# programming.net
KiCad netlist of a schematic drawn in Altium Designer
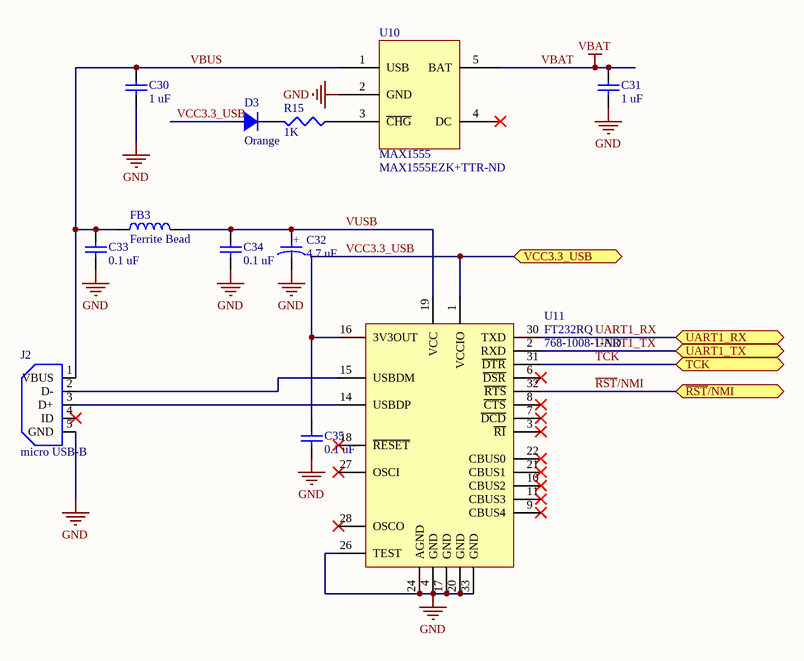
[diagram p0: programming.SchDoc]

(export (version "E")
  (design (tool "Eeschema 10.0.6"))
  (components
    (comp (ref "C30")
      (value "1 uF")
      (footprint "0402")
      (description "Ceramic capacitor, 1 uF, 0402 package")
      (fields (field (name "TOLERANCE") "10%") (field (name "Comment") "Ceramic capacitor"))
      (libsource (lib "rlc") (part "C_1u_0402_ceramic"))
    )
    (comp (ref "C31")
      (value "1 uF")
      (footprint "0402")
      (description "Ceramic capacitor, 1 uF, 0402 package")
      (fields (field (name "TOLERANCE") "10%") (field (name "Comment") "Ceramic capacitor"))
      (libsource (lib "rlc") (part "C_1u_0402_ceramic"))
    )
    (comp (ref "C32")
      (value "4.7 uF")
      (footprint "0603 - Polar Marking")
      (description "Tantalum capacitor, 4.7 uF, 0603 package")
      (fields (field (name "TOLERANCE") "20%") (field (name "Comment") "Tantalum capacitor"))
      (libsource (lib "rlc") (part "C_4.7u_0603_tantalum"))
    )
    (comp (ref "C33")
      (value "0.1 uF")
      (footprint "0402")
      (description "Ceramic capacitor, 0.1u, 0402 package")
      (fields (field (name "TOLERANCE") "10%") (field (name "Comment") "Ceramic capacitor"))
      (libsource (lib "rlc") (part "C_0.1u_0402_ceramic"))
    )
    (comp (ref "C34")
      (value "0.1 uF")
      (footprint "0402")
      (description "Ceramic capacitor, 0.1u, 0402 package")
      (fields (field (name "TOLERANCE") "10%") (field (name "Comment") "Ceramic capacitor"))
      (libsource (lib "rlc") (part "C_0.1u_0402_ceramic"))
    )
    (comp (ref "C35")
      (value "0.1 uF")
      (footprint "0402")
      (description "Ceramic capacitor, 0.1u, 0402 package")
      (fields (field (name "TOLERANCE") "10%") (field (name "Comment") "Ceramic capacitor"))
      (libsource (lib "rlc") (part "C_0.1u_0402_ceramic"))
    )
    (comp (ref "D3")
      (value "LED, Orange")
      (footprint "0402 - DIODE")
      (description "LED, Orange, 0402")
      (fields (field (name "COLOR") "Orange"))
      (libsource (lib "rlc") (part "D_LED_ORANGE_0402"))
    )
    (comp (ref "FB3")
      (value "Ferrite Bead")
      (footprint "0402")
      (description "Ferrite Bead, 150 mA, 0402 package")
      (libsource (lib "rlc") (part "FB_150mA_0402"))
    )
    (comp (ref "J2")
      (value "micro USB-B")
      (footprint "Micro USB-B")
      (description "CONN USB MICRO B RECPT SMT R/A")
      (libsource (lib "opo") (part "Micro USB"))
    )
    (comp (ref "R15")
      (value "1K")
      (footprint "0402")
      (description "Chip resistor, 1K, 0402 package")
      (fields (field (name "TOLERANCE") "1%") (field (name "POWER") "1/16 W"))
      (libsource (lib "rlc") (part "R_1K_0402"))
    )
    (comp (ref "U10")
      (value "MAX1555")
      (footprint "SOT23-5")
      (description "3 Dual-Input USB/AC Adapter 1-Cell Li+  Battery Chargers")
      (fields (field (name "SUPPLIER PART NUMBER 1") "MAX1555EZK+TTR-ND"))
      (libsource (lib "opo") (part "MAX1555"))
    )
    (comp (ref "U11")
      (value "FT232RQ")
      (footprint "QFN-32")
      (description "FT232R USB UART")
      (fields (field (name "SUPPLIER PART NUMBER 1") "768-1008-1-ND"))
      (libsource (lib "opo") (part "IC_FT232RQ"))
    )
  )
  (nets
    (net (code "1") (name "/TCK") (class "Default")
      (node (ref "U11") (pin "31") (pinfunction "~{DTR}_31") (pintype "passive"))
    )
    (net (code "2") (name "/UART1_RX") (class "Default")
      (node (ref "U11") (pin "30") (pinfunction "TXD_30") (pintype "passive"))
    )
    (net (code "3") (name "/UART1_TX") (class "Default")
      (node (ref "U11") (pin "2") (pinfunction "RXD_2") (pintype "passive"))
    )
    (net (code "4") (name "/VBUS") (class "Default")
      (node (ref "C30") (pin "1") (pintype "passive"))
      (node (ref "C33") (pin "1") (pintype "passive"))
      (node (ref "FB3") (pin "2") (pintype "passive"))
      (node (ref "J2") (pin "1") (pinfunction "VBUS_1") (pintype "power_in"))
      (node (ref "U10") (pin "1") (pinfunction "USB_1") (pintype "passive"))
    )
    (net (code "5") (name "/VCC3.3_USB") (class "Default")
      (node (ref "C35") (pin "1") (pintype "passive"))
      (node (ref "D3") (pin "1") (pintype "passive"))
      (node (ref "U11") (pin "1") (pinfunction "VCCIO_1") (pintype "passive"))
      (node (ref "U11") (pin "16") (pinfunction "3V3OUT_16") (pintype "passive"))
    )
    (net (code "6") (name "/VUSB") (class "Default")
      (node (ref "C32") (pin "1") (pintype "passive"))
      (node (ref "C34") (pin "1") (pintype "passive"))
      (node (ref "FB3") (pin "1") (pintype "passive"))
      (node (ref "U11") (pin "19") (pinfunction "VCC_19") (pintype "passive"))
    )
    (net (code "7") (name "/~{RST}{slash}NMI") (class "Default")
      (node (ref "U11") (pin "32") (pinfunction "~{RTS}_32") (pintype "passive"))
    )
    (net (code "8") (name "GND") (class "Default")
      (node (ref "C30") (pin "2") (pintype "passive"))
      (node (ref "C31") (pin "2") (pintype "passive"))
      (node (ref "C32") (pin "2") (pintype "passive"))
      (node (ref "C33") (pin "2") (pintype "passive"))
      (node (ref "C34") (pin "2") (pintype "passive"))
      (node (ref "C35") (pin "2") (pintype "passive"))
      (node (ref "J2") (pin "5") (pinfunction "GND_5") (pintype "power_in"))
      (node (ref "U10") (pin "2") (pinfunction "GND_2") (pintype "passive"))
      (node (ref "U11") (pin "17") (pinfunction "GND_17") (pintype "passive"))
      (node (ref "U11") (pin "20") (pinfunction "GND_20") (pintype "passive"))
      (node (ref "U11") (pin "24") (pinfunction "AGND_24") (pintype "passive"))
      (node (ref "U11") (pin "26") (pinfunction "TEST_26") (pintype "passive"))
      (node (ref "U11") (pin "33") (pinfunction "GND_33") (pintype "passive"))
      (node (ref "U11") (pin "4") (pinfunction "GND_4") (pintype "passive"))
    )
    (net (code "9") (name "Net-(D3-Pad2)") (class "Default")
      (node (ref "D3") (pin "2") (pintype "passive"))
      (node (ref "R15") (pin "1") (pintype "passive"))
    )
    (net (code "10") (name "Net-(J2-D+)") (class "Default")
      (node (ref "J2") (pin "3") (pinfunction "D+_3") (pintype "power_in"))
      (node (ref "U11") (pin "14") (pinfunction "USBDP_14") (pintype "passive"))
    )
    (net (code "11") (name "Net-(J2-D-)") (class "Default")
      (node (ref "J2") (pin "2") (pinfunction "D-_2") (pintype "power_in"))
      (node (ref "U11") (pin "15") (pinfunction "USBDM_15") (pintype "passive"))
    )
    (net (code "12") (name "Net-(U10-~{CHG})") (class "Default")
      (node (ref "R15") (pin "2") (pintype "passive"))
      (node (ref "U10") (pin "3") (pinfunction "~{CHG}_3") (pintype "passive"))
    )
    (net (code "13") (name "VBAT") (class "Default")
      (node (ref "C31") (pin "1") (pintype "passive"))
      (node (ref "U10") (pin "5") (pinfunction "BAT_5") (pintype "passive"))
    )
    (net (code "14") (name "unconnected-(J2-ID-Pad4)") (class "Default")
      (node (ref "J2") (pin "4") (pinfunction "ID_4") (pintype "power_in+no_connect"))
    )
    (net (code "15") (name "unconnected-(U10-DC-Pad4)") (class "Default")
      (node (ref "U10") (pin "4") (pinfunction "DC_4") (pintype "passive+no_connect"))
    )
    (net (code "16") (name "unconnected-(U11-CBUS0-Pad22)") (class "Default")
      (node (ref "U11") (pin "22") (pinfunction "CBUS0_22") (pintype "passive+no_connect"))
    )
    (net (code "17") (name "unconnected-(U11-CBUS1-Pad21)") (class "Default")
      (node (ref "U11") (pin "21") (pinfunction "CBUS1_21") (pintype "passive+no_connect"))
    )
    (net (code "18") (name "unconnected-(U11-CBUS2-Pad10)") (class "Default")
      (node (ref "U11") (pin "10") (pinfunction "CBUS2_10") (pintype "passive+no_connect"))
    )
    (net (code "19") (name "unconnected-(U11-CBUS3-Pad11)") (class "Default")
      (node (ref "U11") (pin "11") (pinfunction "CBUS3_11") (pintype "passive+no_connect"))
    )
    (net (code "20") (name "unconnected-(U11-CBUS4-Pad9)") (class "Default")
      (node (ref "U11") (pin "9") (pinfunction "CBUS4_9") (pintype "passive+no_connect"))
    )
    (net (code "21") (name "unconnected-(U11-OSCI-Pad27)") (class "Default")
      (node (ref "U11") (pin "27") (pinfunction "OSCI_27") (pintype "passive+no_connect"))
    )
    (net (code "22") (name "unconnected-(U11-OSCO-Pad28)") (class "Default")
      (node (ref "U11") (pin "28") (pinfunction "OSCO_28") (pintype "passive+no_connect"))
    )
    (net (code "23") (name "unconnected-(U11-~{CTS}-Pad8)") (class "Default")
      (node (ref "U11") (pin "8") (pinfunction "~{CTS}_8") (pintype "passive+no_connect"))
    )
    (net (code "24") (name "unconnected-(U11-~{DCD}-Pad7)") (class "Default")
      (node (ref "U11") (pin "7") (pinfunction "~{DCD}_7") (pintype "passive+no_connect"))
    )
    (net (code "25") (name "unconnected-(U11-~{DSR}-Pad6)") (class "Default")
      (node (ref "U11") (pin "6") (pinfunction "~{DSR}_6") (pintype "passive+no_connect"))
    )
    (net (code "26") (name "unconnected-(U11-~{RESET}-Pad18)") (class "Default")
      (node (ref "U11") (pin "18") (pinfunction "~{RESET}_18") (pintype "passive+no_connect"))
    )
    (net (code "27") (name "unconnected-(U11-~{RI}-Pad3)") (class "Default")
      (node (ref "U11") (pin "3") (pinfunction "~{RI}_3") (pintype "passive+no_connect"))
    )
  )
)
